# 44con2013.net
KiCad netlist of a schematic drawn in EAGLE
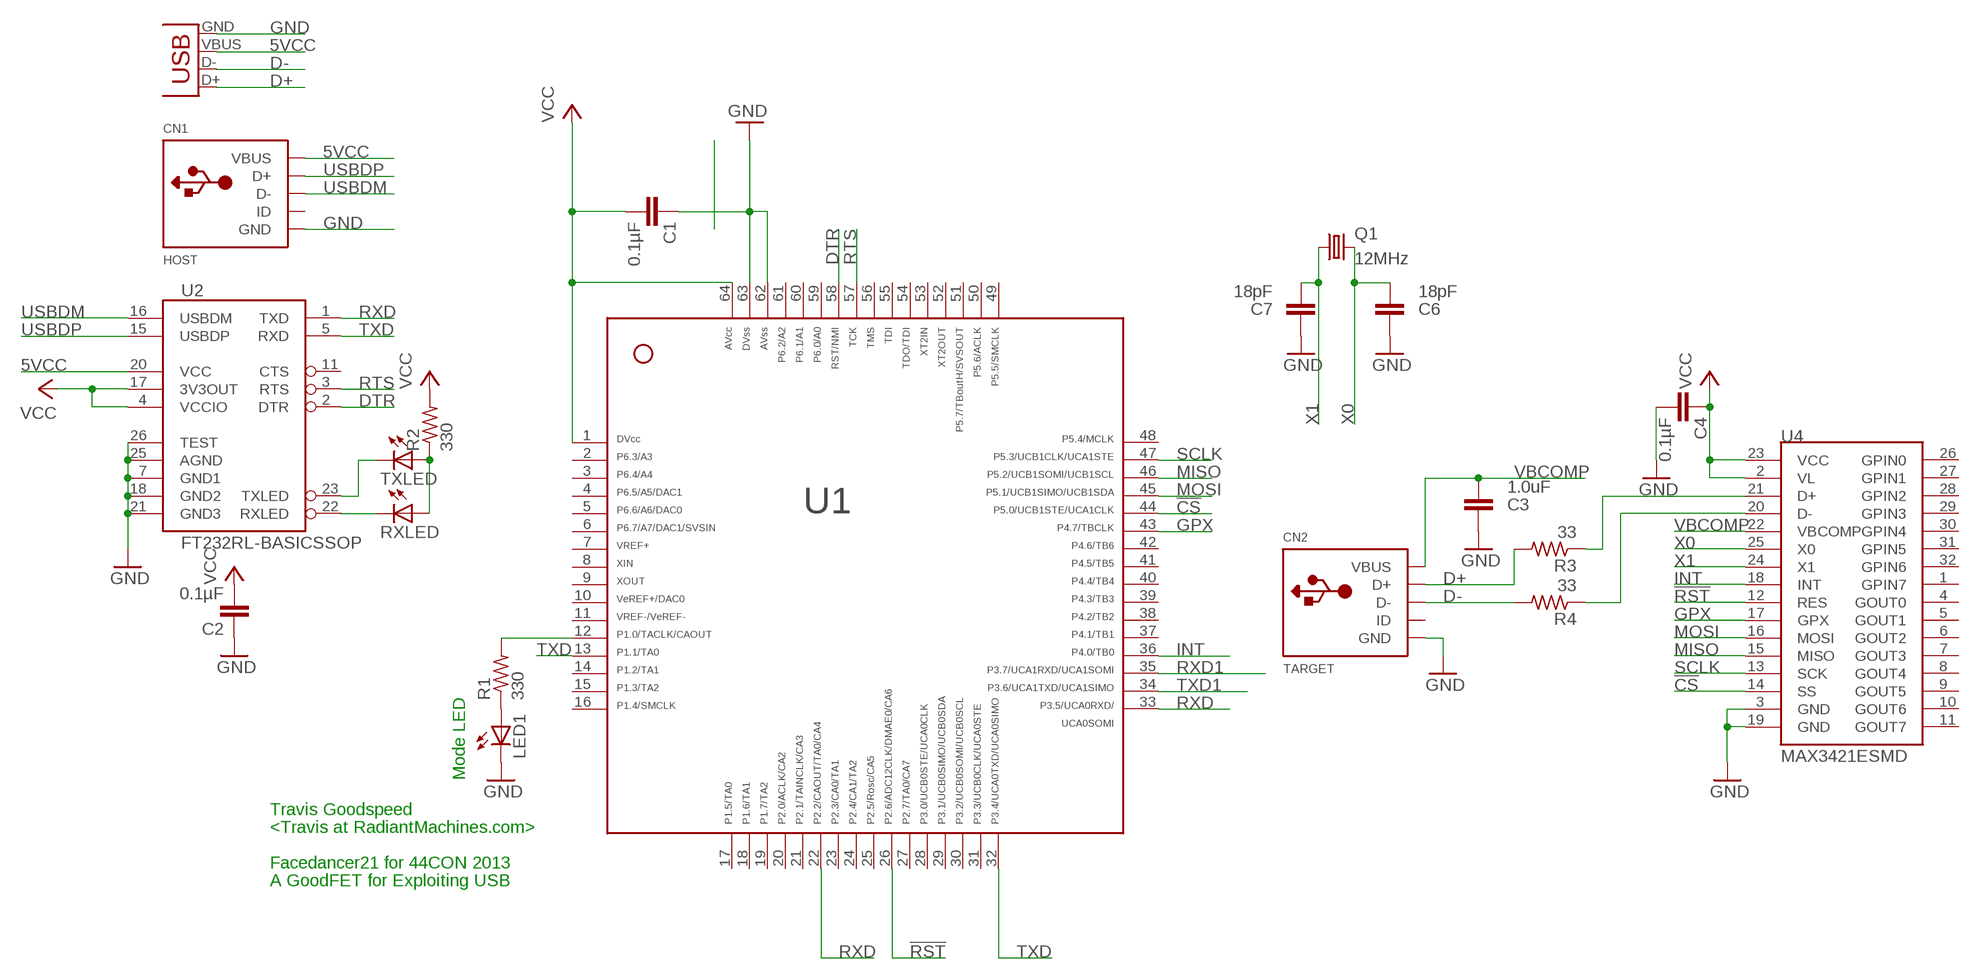
[diagram p0: schematic, sheet 1]

(export (version "E")
  (design (tool "Eeschema 10.0.6"))
  (components
    (comp (ref "C1")
      (value "0.1µF")
      (footprint "eagle-import:C0603")
      (libsource (lib "eagle-import") (part "C-EUC0603"))
    )
    (comp (ref "C2")
      (value "0.1µF")
      (footprint "eagle-import:C0603")
      (libsource (lib "eagle-import") (part "C-EUC0603"))
    )
    (comp (ref "C3")
      (value "1.0uF")
      (footprint "eagle-import:C0603")
      (libsource (lib "eagle-import") (part "C-EUC0603"))
    )
    (comp (ref "C4")
      (value "0.1µF")
      (footprint "eagle-import:C0603")
      (libsource (lib "eagle-import") (part "C-EUC0603"))
    )
    (comp (ref "C6")
      (value "18pF")
      (footprint "eagle-import:C0603")
      (libsource (lib "eagle-import") (part "C-EUC0603"))
    )
    (comp (ref "C7")
      (value "18pF")
      (footprint "eagle-import:C0603")
      (libsource (lib "eagle-import") (part "C-EUC0603"))
    )
    (comp (ref "CN1")
      (value "HOST")
      (footprint "eagle-import:USB-MINIB")
      (libsource (lib "eagle-import") (part "USBMINIB"))
    )
    (comp (ref "CN2")
      (value "TARGET")
      (footprint "eagle-import:USB-MINIB")
      (libsource (lib "eagle-import") (part "USBMINIB"))
    )
    (comp (ref "CN3")
      (value "USB-A-S")
      (footprint "eagle-import:USB-A-S")
      (libsource (lib "eagle-import") (part "USB-A-S"))
    )
    (comp (ref "LED1")
      (value "LEDCHIP-LED0603")
      (footprint "eagle-import:CHIP-LED0603")
      (libsource (lib "eagle-import") (part "LEDCHIP-LED0603"))
    )
    (comp (ref "Q1")
      (value "12MHz")
      (footprint "eagle-import:HC49UP")
      (libsource (lib "eagle-import") (part "CRYSTALHC49UP"))
    )
    (comp (ref "R1")
      (value "330")
      (footprint "eagle-import:R0603")
      (libsource (lib "eagle-import") (part "R-US_R0603"))
    )
    (comp (ref "R2")
      (value "330")
      (footprint "eagle-import:R0603")
      (libsource (lib "eagle-import") (part "R-US_R0603"))
    )
    (comp (ref "R3")
      (value "33")
      (footprint "eagle-import:R0603")
      (libsource (lib "eagle-import") (part "R-US_R0603"))
    )
    (comp (ref "R4")
      (value "33")
      (footprint "eagle-import:R0603")
      (libsource (lib "eagle-import") (part "R-US_R0603"))
    )
    (comp (ref "RXLED")
      (value "LEDCHIP-LED0603")
      (footprint "eagle-import:CHIP-LED0603")
      (libsource (lib "eagle-import") (part "LEDCHIP-LED0603"))
    )
    (comp (ref "TXLED")
      (value "LEDCHIP-LED0603")
      (footprint "eagle-import:CHIP-LED0603")
      (libsource (lib "eagle-import") (part "LEDCHIP-LED0603"))
    )
    (comp (ref "U1")
      (value "F261X---PM64")
      (footprint "eagle-import:PM_PAG64")
      (libsource (lib "eagle-import") (part "F261X---PM64"))
    )
    (comp (ref "U2")
      (value "FT232RL-BASICSSOP")
      (footprint "eagle-import:SSOP28DB")
      (libsource (lib "eagle-import") (part "FT232RL-BASICSSOP"))
    )
    (comp (ref "U4")
      (value "MAX3421ESMD")
      (footprint "eagle-import:TQFP32-5MM")
      (libsource (lib "eagle-import") (part "MAX3421ESMD"))
    )
  )
  (nets
    (net (code "1") (name "/5VCC") (class "Default")
      (node (ref "CN1") (pin "VBUS") (pinfunction "VBUS_VBUS") (pintype "power_in"))
      (node (ref "CN3") (pin "VBUS") (pinfunction "VBUS_VBUS") (pintype "bidirectional"))
      (node (ref "U2") (pin "20") (pinfunction "VCC_20") (pintype "power_in"))
    )
    (net (code "2") (name "/D+") (class "Default")
      (node (ref "CN2") (pin "D+") (pinfunction "D+_D+") (pintype "bidirectional"))
      (node (ref "CN3") (pin "D+") (pinfunction "D+_D+") (pintype "bidirectional"))
      (node (ref "R3") (pin "2") (pinfunction "2_2") (pintype "passive"))
    )
    (net (code "3") (name "/D-") (class "Default")
      (node (ref "CN2") (pin "D-") (pinfunction "D-_D-") (pintype "bidirectional"))
      (node (ref "CN3") (pin "D-") (pinfunction "D-_D-") (pintype "bidirectional"))
      (node (ref "R4") (pin "2") (pinfunction "2_2") (pintype "passive"))
    )
    (net (code "4") (name "/DTR") (class "Default")
      (node (ref "U1") (pin "58") (pinfunction "58_58") (pintype "input"))
      (node (ref "U2") (pin "2") (pinfunction "DTR_2") (pintype "bidirectional"))
    )
    (net (code "5") (name "/GPX") (class "Default")
      (node (ref "U1") (pin "43") (pinfunction "43_43") (pintype "bidirectional"))
      (node (ref "U4") (pin "17") (pinfunction "GPX_17") (pintype "bidirectional"))
    )
    (net (code "6") (name "/INT") (class "Default")
      (node (ref "U1") (pin "36") (pinfunction "36_36") (pintype "output"))
      (node (ref "U4") (pin "18") (pinfunction "INT_18") (pintype "bidirectional"))
    )
    (net (code "7") (name "/MISO") (class "Default")
      (node (ref "U1") (pin "46") (pinfunction "46_46") (pintype "bidirectional"))
      (node (ref "U4") (pin "15") (pinfunction "MISO_15") (pintype "bidirectional"))
    )
    (net (code "8") (name "/MOSI") (class "Default")
      (node (ref "U1") (pin "45") (pinfunction "45_45") (pintype "bidirectional"))
      (node (ref "U4") (pin "16") (pinfunction "MOSI_16") (pintype "bidirectional"))
    )
    (net (code "9") (name "/RTS") (class "Default")
      (node (ref "U1") (pin "57") (pinfunction "57_57") (pintype "input"))
      (node (ref "U2") (pin "3") (pinfunction "RTS_3") (pintype "bidirectional"))
    )
    (net (code "10") (name "/RXD") (class "Default")
      (node (ref "U1") (pin "22") (pinfunction "22_22") (pintype "bidirectional"))
      (node (ref "U1") (pin "33") (pinfunction "33_33") (pintype "bidirectional"))
      (node (ref "U2") (pin "1") (pinfunction "TXD_1") (pintype "output"))
    )
    (net (code "11") (name "/RXD1") (class "Default")
      (node (ref "U1") (pin "35") (pinfunction "35_35") (pintype "bidirectional"))
    )
    (net (code "12") (name "/SCLK") (class "Default")
      (node (ref "U1") (pin "47") (pinfunction "47_47") (pintype "bidirectional"))
      (node (ref "U4") (pin "13") (pinfunction "SCK_13") (pintype "bidirectional"))
    )
    (net (code "13") (name "/TXD") (class "Default")
      (node (ref "U1") (pin "13") (pinfunction "13_13") (pintype "bidirectional"))
      (node (ref "U1") (pin "32") (pinfunction "32_32") (pintype "bidirectional"))
      (node (ref "U2") (pin "5") (pinfunction "RXD_5") (pintype "input"))
    )
    (net (code "14") (name "/TXD1") (class "Default")
      (node (ref "U1") (pin "34") (pinfunction "34_34") (pintype "bidirectional"))
    )
    (net (code "15") (name "/USBDM") (class "Default")
      (node (ref "CN1") (pin "D-") (pinfunction "D-_D-") (pintype "bidirectional"))
      (node (ref "U2") (pin "16") (pinfunction "USBDM_16") (pintype "bidirectional"))
    )
    (net (code "16") (name "/USBDP") (class "Default")
      (node (ref "CN1") (pin "D+") (pinfunction "D+_D+") (pintype "bidirectional"))
      (node (ref "U2") (pin "15") (pinfunction "USBDP_15") (pintype "bidirectional"))
    )
    (net (code "17") (name "/VBCOMP") (class "Default")
      (node (ref "C3") (pin "2") (pinfunction "2_2") (pintype "passive"))
      (node (ref "CN2") (pin "VBUS") (pinfunction "VBUS_VBUS") (pintype "power_in"))
      (node (ref "U4") (pin "22") (pinfunction "VBCOMP_22") (pintype "bidirectional"))
    )
    (net (code "18") (name "/X0") (class "Default")
      (node (ref "C6") (pin "2") (pinfunction "2_2") (pintype "passive"))
      (node (ref "Q1") (pin "2") (pinfunction "2_2") (pintype "passive"))
      (node (ref "U4") (pin "25") (pinfunction "X0_25") (pintype "bidirectional"))
    )
    (net (code "19") (name "/X1") (class "Default")
      (node (ref "C7") (pin "2") (pinfunction "2_2") (pintype "passive"))
      (node (ref "Q1") (pin "1") (pinfunction "1_1") (pintype "passive"))
      (node (ref "U4") (pin "24") (pinfunction "X1_24") (pintype "bidirectional"))
    )
    (net (code "20") (name "/~{CS}") (class "Default")
      (node (ref "U1") (pin "44") (pinfunction "44_44") (pintype "bidirectional"))
      (node (ref "U4") (pin "14") (pinfunction "SS_14") (pintype "bidirectional"))
    )
    (net (code "21") (name "/~{RST}") (class "Default")
      (node (ref "U1") (pin "26") (pinfunction "26_26") (pintype "bidirectional"))
      (node (ref "U4") (pin "12") (pinfunction "RES_12") (pintype "bidirectional"))
    )
    (net (code "22") (name "GND") (class "Default")
      (node (ref "C1") (pin "1") (pinfunction "1_1") (pintype "passive"))
      (node (ref "C2") (pin "1") (pinfunction "1_1") (pintype "passive"))
      (node (ref "C3") (pin "1") (pinfunction "1_1") (pintype "passive"))
      (node (ref "C4") (pin "2") (pinfunction "2_2") (pintype "passive"))
      (node (ref "C6") (pin "1") (pinfunction "1_1") (pintype "passive"))
      (node (ref "C7") (pin "1") (pinfunction "1_1") (pintype "passive"))
      (node (ref "CN1") (pin "GND") (pinfunction "GND_GND") (pintype "power_in"))
      (node (ref "CN2") (pin "GND") (pinfunction "GND_GND") (pintype "power_in"))
      (node (ref "CN3") (pin "GND") (pinfunction "GND_GND") (pintype "bidirectional"))
      (node (ref "LED1") (pin "C") (pinfunction "C_C") (pintype "passive"))
      (node (ref "U1") (pin "62") (pinfunction "62_62") (pintype "power_in"))
      (node (ref "U1") (pin "63") (pinfunction "63_63") (pintype "power_in"))
      (node (ref "U2") (pin "18") (pinfunction "GND2_18") (pintype "power_in"))
      (node (ref "U2") (pin "21") (pinfunction "GND3_21") (pintype "power_in"))
      (node (ref "U2") (pin "25") (pinfunction "AGND_25") (pintype "power_in"))
      (node (ref "U2") (pin "26") (pinfunction "TEST_26") (pintype "input"))
      (node (ref "U2") (pin "7") (pinfunction "GND1_7") (pintype "power_in"))
      (node (ref "U4") (pin "19") (pinfunction "GND_19") (pintype "bidirectional"))
      (node (ref "U4") (pin "3") (pinfunction "GND_3") (pintype "bidirectional"))
    )
    (net (code "23") (name "Net-(LED1-PadA)") (class "Default")
      (node (ref "LED1") (pin "A") (pinfunction "A_A") (pintype "passive"))
      (node (ref "R1") (pin "1") (pinfunction "1_1") (pintype "passive"))
    )
    (net (code "24") (name "Net-(R1-Pad2)") (class "Default")
      (node (ref "R1") (pin "2") (pinfunction "2_2") (pintype "passive"))
      (node (ref "U1") (pin "12") (pinfunction "12_12") (pintype "bidirectional"))
    )
    (net (code "25") (name "Net-(R2-Pad1)") (class "Default")
      (node (ref "R2") (pin "1") (pinfunction "1_1") (pintype "passive"))
      (node (ref "RXLED") (pin "A") (pinfunction "A_A") (pintype "passive"))
      (node (ref "TXLED") (pin "A") (pinfunction "A_A") (pintype "passive"))
    )
    (net (code "26") (name "Net-(U2-RXLED)") (class "Default")
      (node (ref "RXLED") (pin "C") (pinfunction "C_C") (pintype "passive"))
      (node (ref "U2") (pin "22") (pinfunction "RXLED_22") (pintype "bidirectional"))
    )
    (net (code "27") (name "Net-(U2-TXLED)") (class "Default")
      (node (ref "TXLED") (pin "C") (pinfunction "C_C") (pintype "passive"))
      (node (ref "U2") (pin "23") (pinfunction "TXLED_23") (pintype "bidirectional"))
    )
    (net (code "28") (name "Net-(U4-D+)") (class "Default")
      (node (ref "R3") (pin "1") (pinfunction "1_1") (pintype "passive"))
      (node (ref "U4") (pin "21") (pinfunction "D+_21") (pintype "bidirectional"))
    )
    (net (code "29") (name "Net-(U4-D-)") (class "Default")
      (node (ref "R4") (pin "1") (pinfunction "1_1") (pintype "passive"))
      (node (ref "U4") (pin "20") (pinfunction "D-_20") (pintype "bidirectional"))
    )
    (net (code "30") (name "VCC") (class "Default")
      (node (ref "C1") (pin "2") (pinfunction "2_2") (pintype "passive"))
      (node (ref "C2") (pin "2") (pinfunction "2_2") (pintype "passive"))
      (node (ref "C4") (pin "1") (pinfunction "1_1") (pintype "passive"))
      (node (ref "R2") (pin "2") (pinfunction "2_2") (pintype "passive"))
      (node (ref "U1") (pin "1") (pinfunction "1_1") (pintype "power_in"))
      (node (ref "U1") (pin "64") (pinfunction "64_64") (pintype "power_in"))
      (node (ref "U2") (pin "17") (pinfunction "3V3OUT_17") (pintype "output"))
      (node (ref "U2") (pin "4") (pinfunction "VCCIO_4") (pintype "power_in"))
      (node (ref "U4") (pin "2") (pinfunction "VL_2") (pintype "bidirectional"))
      (node (ref "U4") (pin "23") (pinfunction "VCC_23") (pintype "bidirectional"))
    )
    (net (code "31") (name "unconnected-(CN1-PadID)") (class "Default")
      (node (ref "CN1") (pin "ID") (pinfunction "ID_ID") (pintype "bidirectional"))
    )
    (net (code "32") (name "unconnected-(CN2-PadID)") (class "Default")
      (node (ref "CN2") (pin "ID") (pinfunction "ID_ID") (pintype "bidirectional"))
    )
    (net (code "33") (name "unconnected-(U1-Pad2)") (class "Default")
      (node (ref "U1") (pin "2") (pinfunction "2_2") (pintype "bidirectional"))
    )
    (net (code "34") (name "unconnected-(U1-Pad3)") (class "Default")
      (node (ref "U1") (pin "3") (pinfunction "3_3") (pintype "bidirectional"))
    )
    (net (code "35") (name "unconnected-(U1-Pad4)") (class "Default")
      (node (ref "U1") (pin "4") (pinfunction "4_4") (pintype "bidirectional"))
    )
    (net (code "36") (name "unconnected-(U1-Pad5)") (class "Default")
      (node (ref "U1") (pin "5") (pinfunction "5_5") (pintype "bidirectional"))
    )
    (net (code "37") (name "unconnected-(U1-Pad6)") (class "Default")
      (node (ref "U1") (pin "6") (pinfunction "6_6") (pintype "bidirectional"))
    )
    (net (code "38") (name "unconnected-(U1-Pad7)") (class "Default")
      (node (ref "U1") (pin "7") (pinfunction "7_7") (pintype "output"))
    )
    (net (code "39") (name "unconnected-(U1-Pad8)") (class "Default")
      (node (ref "U1") (pin "8") (pinfunction "8_8") (pintype "input"))
    )
    (net (code "40") (name "unconnected-(U1-Pad9)") (class "Default")
      (node (ref "U1") (pin "9") (pinfunction "9_9") (pintype "output"))
    )
    (net (code "41") (name "unconnected-(U1-Pad10)") (class "Default")
      (node (ref "U1") (pin "10") (pinfunction "10_10") (pintype "bidirectional"))
    )
    (net (code "42") (name "unconnected-(U1-Pad11)") (class "Default")
      (node (ref "U1") (pin "11") (pinfunction "11_11") (pintype "bidirectional"))
    )
    (net (code "43") (name "unconnected-(U1-Pad14)") (class "Default")
      (node (ref "U1") (pin "14") (pinfunction "14_14") (pintype "bidirectional"))
    )
    (net (code "44") (name "unconnected-(U1-Pad15)") (class "Default")
      (node (ref "U1") (pin "15") (pinfunction "15_15") (pintype "bidirectional"))
    )
    (net (code "45") (name "unconnected-(U1-Pad16)") (class "Default")
      (node (ref "U1") (pin "16") (pinfunction "16_16") (pintype "bidirectional"))
    )
    (net (code "46") (name "unconnected-(U1-Pad17)") (class "Default")
      (node (ref "U1") (pin "17") (pinfunction "17_17") (pintype "bidirectional"))
    )
    (net (code "47") (name "unconnected-(U1-Pad18)") (class "Default")
      (node (ref "U1") (pin "18") (pinfunction "18_18") (pintype "bidirectional"))
    )
    (net (code "48") (name "unconnected-(U1-Pad19)") (class "Default")
      (node (ref "U1") (pin "19") (pinfunction "19_19") (pintype "bidirectional"))
    )
    (net (code "49") (name "unconnected-(U1-Pad20)") (class "Default")
      (node (ref "U1") (pin "20") (pinfunction "20_20") (pintype "bidirectional"))
    )
    (net (code "50") (name "unconnected-(U1-Pad21)") (class "Default")
      (node (ref "U1") (pin "21") (pinfunction "21_21") (pintype "bidirectional"))
    )
    (net (code "51") (name "unconnected-(U1-Pad23)") (class "Default")
      (node (ref "U1") (pin "23") (pinfunction "23_23") (pintype "bidirectional"))
    )
    (net (code "52") (name "unconnected-(U1-Pad24)") (class "Default")
      (node (ref "U1") (pin "24") (pinfunction "24_24") (pintype "bidirectional"))
    )
    (net (code "53") (name "unconnected-(U1-Pad25)") (class "Default")
      (node (ref "U1") (pin "25") (pinfunction "25_25") (pintype "bidirectional"))
    )
    (net (code "54") (name "unconnected-(U1-Pad27)") (class "Default")
      (node (ref "U1") (pin "27") (pinfunction "27_27") (pintype "bidirectional"))
    )
    (net (code "55") (name "unconnected-(U1-Pad28)") (class "Default")
      (node (ref "U1") (pin "28") (pinfunction "28_28") (pintype "bidirectional"))
    )
    (net (code "56") (name "unconnected-(U1-Pad29)") (class "Default")
      (node (ref "U1") (pin "29") (pinfunction "29_29") (pintype "bidirectional"))
    )
    (net (code "57") (name "unconnected-(U1-Pad30)") (class "Default")
      (node (ref "U1") (pin "30") (pinfunction "30_30") (pintype "bidirectional"))
    )
    (net (code "58") (name "unconnected-(U1-Pad31)") (class "Default")
      (node (ref "U1") (pin "31") (pinfunction "31_31") (pintype "bidirectional"))
    )
    (net (code "59") (name "unconnected-(U1-Pad37)") (class "Default")
      (node (ref "U1") (pin "37") (pinfunction "37_37") (pintype "bidirectional"))
    )
    (net (code "60") (name "unconnected-(U1-Pad38)") (class "Default")
      (node (ref "U1") (pin "38") (pinfunction "38_38") (pintype "bidirectional"))
    )
    (net (code "61") (name "unconnected-(U1-Pad39)") (class "Default")
      (node (ref "U1") (pin "39") (pinfunction "39_39") (pintype "bidirectional"))
    )
    (net (code "62") (name "unconnected-(U1-Pad40)") (class "Default")
      (node (ref "U1") (pin "40") (pinfunction "40_40") (pintype "input"))
    )
    (net (code "63") (name "unconnected-(U1-Pad41)") (class "Default")
      (node (ref "U1") (pin "41") (pinfunction "41_41") (pintype "bidirectional"))
    )
    (net (code "64") (name "unconnected-(U1-Pad42)") (class "Default")
      (node (ref "U1") (pin "42") (pinfunction "42_42") (pintype "bidirectional"))
    )
    (net (code "65") (name "unconnected-(U1-Pad48)") (class "Default")
      (node (ref "U1") (pin "48") (pinfunction "48_48") (pintype "bidirectional"))
    )
    (net (code "66") (name "unconnected-(U1-Pad49)") (class "Default")
      (node (ref "U1") (pin "49") (pinfunction "49_49") (pintype "bidirectional"))
    )
    (net (code "67") (name "unconnected-(U1-Pad50)") (class "Default")
      (node (ref "U1") (pin "50") (pinfunction "50_50") (pintype "bidirectional"))
    )
    (net (code "68") (name "unconnected-(U1-Pad51)") (class "Default")
      (node (ref "U1") (pin "51") (pinfunction "51_51") (pintype "bidirectional"))
    )
    (net (code "69") (name "unconnected-(U1-Pad52)") (class "Default")
      (node (ref "U1") (pin "52") (pinfunction "52_52") (pintype "output"))
    )
    (net (code "70") (name "unconnected-(U1-Pad53)") (class "Default")
      (node (ref "U1") (pin "53") (pinfunction "53_53") (pintype "input"))
    )
    (net (code "71") (name "unconnected-(U1-Pad54)") (class "Default")
      (node (ref "U1") (pin "54") (pinfunction "54_54") (pintype "bidirectional"))
    )
    (net (code "72") (name "unconnected-(U1-Pad55)") (class "Default")
      (node (ref "U1") (pin "55") (pinfunction "55_55") (pintype "input"))
    )
    (net (code "73") (name "unconnected-(U1-Pad56)") (class "Default")
      (node (ref "U1") (pin "56") (pinfunction "56_56") (pintype "input"))
    )
    (net (code "74") (name "unconnected-(U1-Pad59)") (class "Default")
      (node (ref "U1") (pin "59") (pinfunction "59_59") (pintype "bidirectional"))
    )
    (net (code "75") (name "unconnected-(U1-Pad60)") (class "Default")
      (node (ref "U1") (pin "60") (pinfunction "60_60") (pintype "bidirectional"))
    )
    (net (code "76") (name "unconnected-(U1-Pad61)") (class "Default")
      (node (ref "U1") (pin "61") (pinfunction "61_61") (pintype "bidirectional"))
    )
    (net (code "77") (name "unconnected-(U2-CTS-Pad11)") (class "Default")
      (node (ref "U2") (pin "11") (pinfunction "CTS_11") (pintype "bidirectional"))
    )
    (net (code "78") (name "unconnected-(U4-GOUT0-Pad4)") (class "Default")
      (node (ref "U4") (pin "4") (pinfunction "GOUT0_4") (pintype "bidirectional"))
    )
    (net (code "79") (name "unconnected-(U4-GOUT1-Pad5)") (class "Default")
      (node (ref "U4") (pin "5") (pinfunction "GOUT1_5") (pintype "bidirectional"))
    )
    (net (code "80") (name "unconnected-(U4-GOUT2-Pad6)") (class "Default")
      (node (ref "U4") (pin "6") (pinfunction "GOUT2_6") (pintype "bidirectional"))
    )
    (net (code "81") (name "unconnected-(U4-GOUT3-Pad7)") (class "Default")
      (node (ref "U4") (pin "7") (pinfunction "GOUT3_7") (pintype "bidirectional"))
    )
    (net (code "82") (name "unconnected-(U4-GOUT4-Pad8)") (class "Default")
      (node (ref "U4") (pin "8") (pinfunction "GOUT4_8") (pintype "bidirectional"))
    )
    (net (code "83") (name "unconnected-(U4-GOUT5-Pad9)") (class "Default")
      (node (ref "U4") (pin "9") (pinfunction "GOUT5_9") (pintype "bidirectional"))
    )
    (net (code "84") (name "unconnected-(U4-GOUT6-Pad10)") (class "Default")
      (node (ref "U4") (pin "10") (pinfunction "GOUT6_10") (pintype "bidirectional"))
    )
    (net (code "85") (name "unconnected-(U4-GOUT7-Pad11)") (class "Default")
      (node (ref "U4") (pin "11") (pinfunction "GOUT7_11") (pintype "bidirectional"))
    )
    (net (code "86") (name "unconnected-(U4-GPIN0-Pad26)") (class "Default")
      (node (ref "U4") (pin "26") (pinfunction "GPIN0_26") (pintype "bidirectional"))
    )
    (net (code "87") (name "unconnected-(U4-GPIN1-Pad27)") (class "Default")
      (node (ref "U4") (pin "27") (pinfunction "GPIN1_27") (pintype "bidirectional"))
    )
    (net (code "88") (name "unconnected-(U4-GPIN2-Pad28)") (class "Default")
      (node (ref "U4") (pin "28") (pinfunction "GPIN2_28") (pintype "bidirectional"))
    )
    (net (code "89") (name "unconnected-(U4-GPIN3-Pad29)") (class "Default")
      (node (ref "U4") (pin "29") (pinfunction "GPIN3_29") (pintype "bidirectional"))
    )
    (net (code "90") (name "unconnected-(U4-GPIN4-Pad30)") (class "Default")
      (node (ref "U4") (pin "30") (pinfunction "GPIN4_30") (pintype "bidirectional"))
    )
    (net (code "91") (name "unconnected-(U4-GPIN5-Pad31)") (class "Default")
      (node (ref "U4") (pin "31") (pinfunction "GPIN5_31") (pintype "bidirectional"))
    )
    (net (code "92") (name "unconnected-(U4-GPIN6-Pad32)") (class "Default")
      (node (ref "U4") (pin "32") (pinfunction "GPIN6_32") (pintype "bidirectional"))
    )
    (net (code "93") (name "unconnected-(U4-GPIN7-Pad1)") (class "Default")
      (node (ref "U4") (pin "1") (pinfunction "GPIN7_1") (pintype "bidirectional"))
    )
  )
)
